# openevse-ac-filter-eagle7.net
KiCad netlist of a schematic drawn in EAGLE
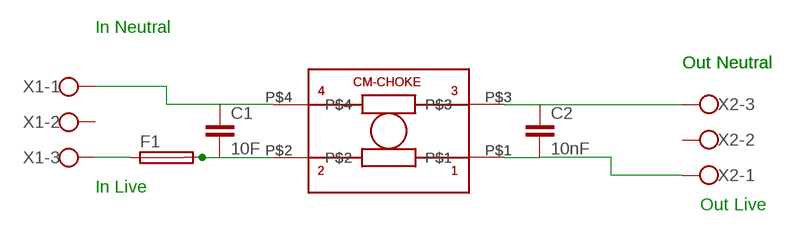
[diagram p0: schematic, sheet 1]

(export (version "E")
  (design (tool "Eeschema 10.0.6"))
  (components
    (comp (ref "C1")
      (value "10F")
      (footprint "eagle-import:C5B2.5")
      (libsource (lib "eagle-import") (part "C5/2.5"))
    )
    (comp (ref "C2")
      (value "10nF")
      (footprint "eagle-import:C5B2.5")
      (libsource (lib "eagle-import") (part "C5/2.5"))
    )
    (comp (ref "F1")
      (value "GSH15")
      (footprint "eagle-import:GSH15")
      (fields (field (name "MPN") "64900001039"))
      (libsource (lib "eagle-import") (part "GSH15"))
    )
    (comp (ref "U$1")
      (value "47mH")
      (footprint "eagle-import:RN114-0.3-02-47M")
      (libsource (lib "eagle-import") (part "RN114-0.3-02-47M"))
    )
    (comp (ref "U$2")
      (value "RN214-0.3-02-47M")
      (footprint "eagle-import:RN214-0.3-02-47M")
      (libsource (lib "eagle-import") (part "RN214-0.3-02-47M"))
    )
    (comp (ref "X1")
      (value "W237-103")
      (footprint "eagle-import:W237-103")
      (fields (field (name "MPN") "237-103"))
      (libsource (lib "eagle-import") (part "W237-103"))
    )
    (comp (ref "X2")
      (value "W237-103")
      (footprint "eagle-import:W237-103")
      (fields (field (name "MPN") "237-103"))
      (libsource (lib "eagle-import") (part "W237-103"))
    )
  )
  (nets
    (net (code "1") (name "Net-(C1-Pad2)") (class "Default")
      (node (ref "C1") (pin "2") (pinfunction "2_2") (pintype "passive"))
      (node (ref "F1") (pin "2") (pinfunction "2_2") (pintype "passive"))
      (node (ref "U$1") (pin "P$2") (pinfunction "P$2_P$2") (pintype "bidirectional"))
      (node (ref "U$2") (pin "P$2") (pinfunction "P$2_P$2") (pintype "bidirectional"))
    )
    (net (code "2") (name "Net-(X1A-KL)") (class "Default")
      (node (ref "C1") (pin "1") (pinfunction "1_1") (pintype "passive"))
      (node (ref "U$1") (pin "P$4") (pinfunction "P$4_P$4") (pintype "bidirectional"))
      (node (ref "U$2") (pin "P$4") (pinfunction "P$4_P$4") (pintype "bidirectional"))
      (node (ref "X1") (pin "1") (pinfunction "KL_1") (pintype "passive"))
    )
    (net (code "3") (name "Net-(X1C-KL)") (class "Default")
      (node (ref "F1") (pin "1") (pinfunction "1_1") (pintype "passive"))
      (node (ref "X1") (pin "3") (pinfunction "KL_3") (pintype "passive"))
    )
    (net (code "4") (name "Net-(X2A-KL)") (class "Default")
      (node (ref "C2") (pin "2") (pinfunction "2_2") (pintype "passive"))
      (node (ref "U$1") (pin "P$1") (pinfunction "P$1_P$1") (pintype "bidirectional"))
      (node (ref "U$2") (pin "P$1") (pinfunction "P$1_P$1") (pintype "bidirectional"))
      (node (ref "X2") (pin "1") (pinfunction "KL_1") (pintype "passive"))
    )
    (net (code "5") (name "Net-(X2C-KL)") (class "Default")
      (node (ref "C2") (pin "1") (pinfunction "1_1") (pintype "passive"))
      (node (ref "U$1") (pin "P$3") (pinfunction "P$3_P$3") (pintype "bidirectional"))
      (node (ref "U$2") (pin "P$3") (pinfunction "P$3_P$3") (pintype "bidirectional"))
      (node (ref "X2") (pin "3") (pinfunction "KL_3") (pintype "passive"))
    )
    (net (code "6") (name "unconnected-(X1B-KL-Pad2)") (class "Default")
      (node (ref "X1") (pin "2") (pinfunction "KL_2") (pintype "passive"))
    )
    (net (code "7") (name "unconnected-(X2B-KL-Pad2)") (class "Default")
      (node (ref "X2") (pin "2") (pinfunction "KL_2") (pintype "passive"))
    )
  )
)
